# schematic.net
KiCad netlist of a schematic drawn in EasyEDA
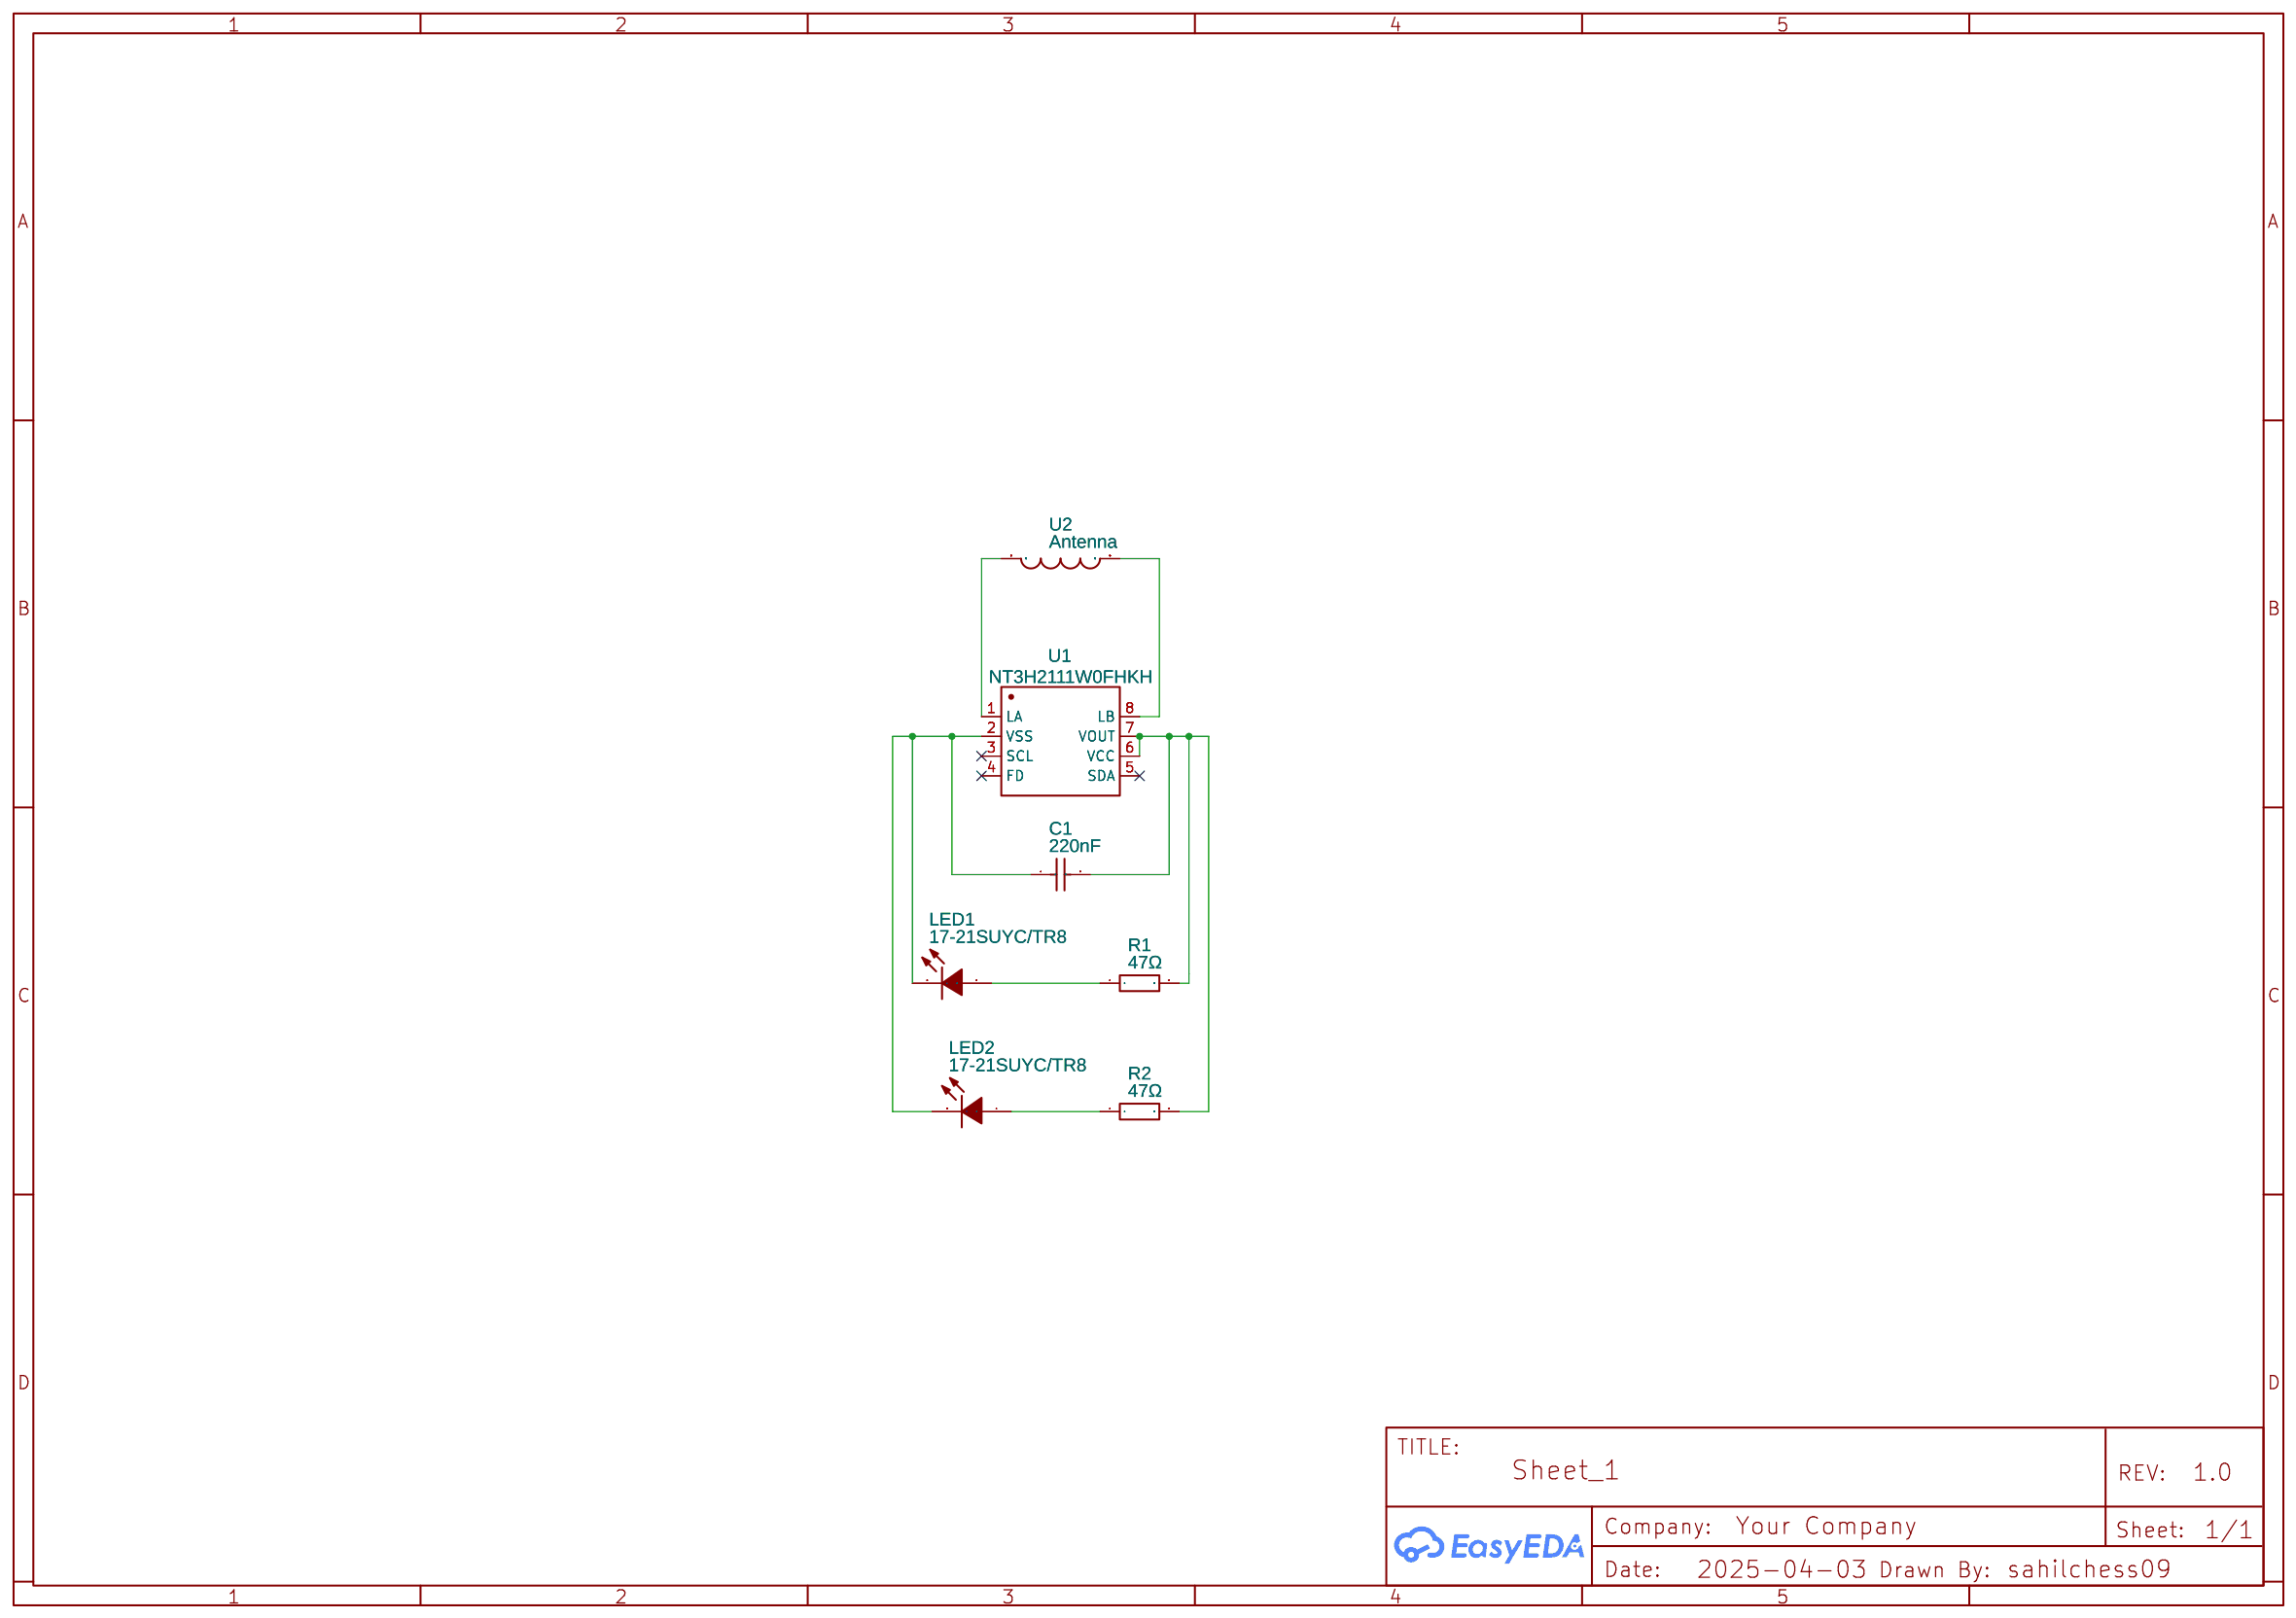
[diagram p0: schematic sheet]

(export (version "E")
  (design (tool "Eeschema 10.0.6"))
  (components
    (comp (ref "C1")
      (value "220nF")
      (fields
        (field (name "Manufacturer Part") "CL10B224KA8NNNC")
        (field (name "Manufacturer") "SAMSUNG(三星)")
      )
      (libsource (lib "") (part "CL10B224KA8NNNC"))
    )
    (comp (ref "LED1")
      (value "17-21SUYC/TR8")
      (fields (field (name "Manufacturer Part") "KT-0805黄灯") (field (name "Manufacturer") "KENTO"))
      (libsource (lib "") (part "17-21SUYC/TR8"))
    )
    (comp (ref "LED2")
      (value "17-21SUYC/TR8")
      (fields (field (name "Manufacturer Part") "KT-0805黄灯") (field (name "Manufacturer") "KENTO"))
      (libsource (lib "") (part "17-21SUYC/TR8"))
    )
    (comp (ref "R1")
      (value "47Ω")
      (fields
        (field (name "Manufacturer Part") "0603WAF470JT5E")
        (field (name "Manufacturer") "UNI-ROYAL(厚声)")
      )
      (libsource (lib "") (part "0603WAF470JT5E"))
    )
    (comp (ref "R2")
      (value "47Ω")
      (fields
        (field (name "Manufacturer Part") "0603WAF470JT5E")
        (field (name "Manufacturer") "UNI-ROYAL(厚声)")
      )
      (libsource (lib "") (part "0603WAF470JT5E"))
    )
    (comp (ref "U1")
      (value "NT3H2111W0FHKH")
      (fields (field (name "Manufacturer") "NXP(恩智浦)"))
      (libsource (lib "") (part "NT3H2111W0FHKH"))
    )
    (comp (ref "U2") (value "Antenna") (libsource (lib "") (part "Antenna")))
  )
  (nets
    (net (code "1") (name "Net-(LED1-+)") (class "Default")
      (node (ref "LED1") (pin "1") (pinfunction "+_1") (pintype "unspecified"))
      (node (ref "R1") (pin "1") (pinfunction "1_1") (pintype "input"))
    )
    (net (code "2") (name "Net-(LED1--)") (class "Default")
      (node (ref "C1") (pin "1") (pinfunction "1_1") (pintype "input"))
      (node (ref "LED1") (pin "2") (pinfunction "-_2") (pintype "unspecified"))
      (node (ref "LED2") (pin "2") (pinfunction "-_2") (pintype "unspecified"))
      (node (ref "U1") (pin "2") (pinfunction "VSS_2") (pintype "unspecified"))
    )
    (net (code "3") (name "Net-(LED2-+)") (class "Default")
      (node (ref "LED2") (pin "1") (pinfunction "+_1") (pintype "unspecified"))
      (node (ref "R2") (pin "1") (pinfunction "1_1") (pintype "input"))
    )
    (net (code "4") (name "Net-(U1-LA)") (class "Default")
      (node (ref "U1") (pin "1") (pinfunction "LA_1") (pintype "unspecified"))
      (node (ref "U2") (pin "P$1") (pinfunction "P$1_P$1") (pintype "unspecified"))
    )
    (net (code "5") (name "Net-(U1-LB)") (class "Default")
      (node (ref "U1") (pin "8") (pinfunction "LB_8") (pintype "unspecified"))
      (node (ref "U2") (pin "P$2") (pinfunction "P$2_P$2") (pintype "unspecified"))
    )
    (net (code "6") (name "Net-(U1-VCC)") (class "Default")
      (node (ref "C1") (pin "2") (pinfunction "2_2") (pintype "input"))
      (node (ref "R1") (pin "2") (pinfunction "2_2") (pintype "input"))
      (node (ref "R2") (pin "2") (pinfunction "2_2") (pintype "input"))
      (node (ref "U1") (pin "6") (pinfunction "VCC_6") (pintype "unspecified"))
      (node (ref "U1") (pin "7") (pinfunction "VOUT_7") (pintype "unspecified"))
    )
    (net (code "7") (name "unconnected-(U1-FD-Pad4)") (class "Default")
      (node (ref "U1") (pin "4") (pinfunction "FD_4") (pintype "unspecified+no_connect"))
    )
    (net (code "8") (name "unconnected-(U1-SCL-Pad3)") (class "Default")
      (node (ref "U1") (pin "3") (pinfunction "SCL_3") (pintype "unspecified+no_connect"))
    )
    (net (code "9") (name "unconnected-(U1-SDA-Pad5)") (class "Default")
      (node (ref "U1") (pin "5") (pinfunction "SDA_5") (pintype "unspecified+no_connect"))
    )
  )
)
